# SignalAnalyse.net
KiCad netlist of a schematic drawn in Altium Designer
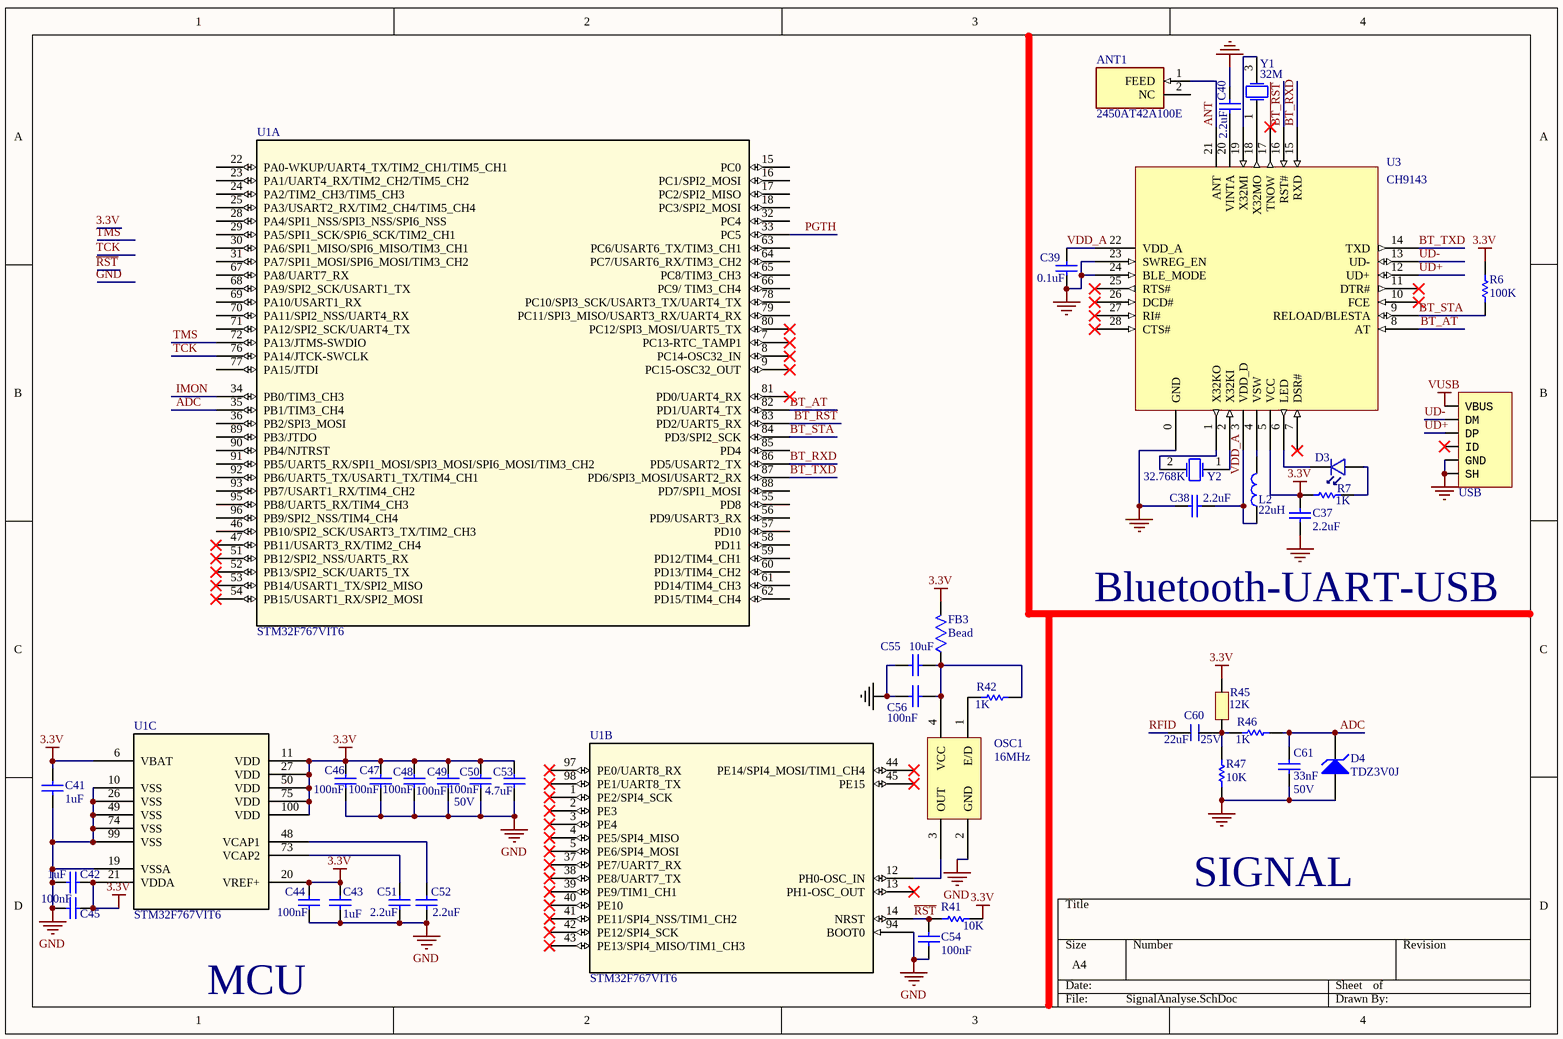
[diagram p0: SignalAnalyse.SchDoc]

(export (version "E")
  (design (tool "Eeschema 10.0.6"))
  (components
    (comp (ref "ANT1")
      (value "2450AT42A100E")
      (footprint "SamacSys:ANTC5020X110N")
      (description "Antenna")
      (fields (field (name "MOUSER PART NUMBER") "609-2450AT42A100E"))
      (libsource (lib "*") (part "2450AT42A100E"))
    )
    (comp (ref "C37")
      (value "2.2uF")
      (footprint "1608[0603]")
      (description "Capacitor (Semiconductor SIM Model)")
      (fields
        (field (name "VOLTAGE") "10V")
        (field (name "Comment") "GRM188R61A226ME15D")
        (field (name "PUBLISHER") "Altium Limited")
      )
      (libsource (lib "Miscellaneous Devices") (part "Cap Semi"))
    )
    (comp (ref "C38")
      (value "2.2uF")
      (footprint "1608[0603]")
      (description "Capacitor (Semiconductor SIM Model)")
      (fields
        (field (name "VOLTAGE") "10V")
        (field (name "Comment") "GRM188R61A226ME15D")
        (field (name "PUBLISHER") "Altium Limited")
      )
      (libsource (lib "Miscellaneous Devices") (part "Cap Semi"))
    )
    (comp (ref "C39")
      (value "0.1uF")
      (footprint "1608[0603]")
      (description "Capacitor (Semiconductor SIM Model)")
      (fields
        (field (name "VOLTAGE") "10V")
        (field (name "Comment") "GRM188R61A226ME15D")
        (field (name "PUBLISHER") "Altium Limited")
      )
      (libsource (lib "Miscellaneous Devices") (part "Cap Semi"))
    )
    (comp (ref "C40")
      (value "2.2uF")
      (footprint "1608[0603]")
      (description "Capacitor (Semiconductor SIM Model)")
      (fields
        (field (name "VOLTAGE") "10V")
        (field (name "Comment") "GRM188R61A226ME15D")
        (field (name "PUBLISHER") "Altium Limited")
      )
      (libsource (lib "Miscellaneous Devices") (part "Cap Semi"))
    )
    (comp (ref "C41")
      (value "1uF")
      (footprint "1608[0603]")
      (description "Capacitor (Semiconductor SIM Model)")
      (fields
        (field (name "VOLTAGE") "50V")
        (field (name "Comment") "GRM188R61A226ME15D")
        (field (name "PUBLISHER") "Altium Limited")
      )
      (libsource (lib "Miscellaneous Devices") (part "Cap Semi"))
    )
    (comp (ref "C42")
      (value "1uF")
      (footprint "1608[0603]")
      (description "Capacitor (Semiconductor SIM Model)")
      (fields
        (field (name "VOLTAGE") "50V")
        (field (name "Comment") "GRM188R61A226ME15D")
        (field (name "PUBLISHER") "Altium Limited")
      )
      (libsource (lib "Miscellaneous Devices") (part "Cap Semi"))
    )
    (comp (ref "C43")
      (value "1uF")
      (footprint "1608[0603]")
      (description "Capacitor (Semiconductor SIM Model)")
      (fields
        (field (name "VOLTAGE") "50V")
        (field (name "Comment") "GRM188R61A226ME15D")
        (field (name "PUBLISHER") "Altium Limited")
      )
      (libsource (lib "Miscellaneous Devices") (part "Cap Semi"))
    )
    (comp (ref "C44")
      (value "100nF")
      (footprint "1608[0603]")
      (description "Capacitor (Semiconductor SIM Model)")
      (fields
        (field (name "VOLTAGE") "50V")
        (field (name "Comment") "GRM188R61A226ME15D")
        (field (name "PUBLISHER") "Altium Limited")
      )
      (libsource (lib "Miscellaneous Devices") (part "Cap Semi"))
    )
    (comp (ref "C45")
      (value "100nF")
      (footprint "1608[0603]")
      (description "Capacitor (Semiconductor SIM Model)")
      (fields
        (field (name "VOLTAGE") "50V")
        (field (name "Comment") "GRM188R61A226ME15D")
        (field (name "PUBLISHER") "Altium Limited")
      )
      (libsource (lib "Miscellaneous Devices") (part "Cap Semi"))
    )
    (comp (ref "C46")
      (value "100nF")
      (footprint "1608[0603]")
      (description "Capacitor (Semiconductor SIM Model)")
      (fields
        (field (name "VOLTAGE") "50V")
        (field (name "Comment") "GRM188R61A226ME15D")
        (field (name "PUBLISHER") "Altium Limited")
      )
      (libsource (lib "Miscellaneous Devices") (part "Cap Semi"))
    )
    (comp (ref "C47")
      (value "100nF")
      (footprint "1608[0603]")
      (description "Capacitor (Semiconductor SIM Model)")
      (fields
        (field (name "VOLTAGE") "50V")
        (field (name "Comment") "GRM188R61A226ME15D")
        (field (name "PUBLISHER") "Altium Limited")
      )
      (libsource (lib "Miscellaneous Devices") (part "Cap Semi"))
    )
    (comp (ref "C48")
      (value "100nF")
      (footprint "1608[0603]")
      (description "Capacitor (Semiconductor SIM Model)")
      (fields
        (field (name "VOLTAGE") "50V")
        (field (name "Comment") "GRM188R61A226ME15D")
        (field (name "PUBLISHER") "Altium Limited")
      )
      (libsource (lib "Miscellaneous Devices") (part "Cap Semi"))
    )
    (comp (ref "C49")
      (value "100nF")
      (footprint "1608[0603]")
      (description "Capacitor (Semiconductor SIM Model)")
      (fields
        (field (name "VOLTAGE") "50V")
        (field (name "Comment") "GRM188R61A226ME15D")
        (field (name "PUBLISHER") "Altium Limited")
      )
      (libsource (lib "Miscellaneous Devices") (part "Cap Semi"))
    )
    (comp (ref "C50")
      (value "100nF")
      (footprint "1608[0603]")
      (description "Capacitor (Semiconductor SIM Model)")
      (fields
        (field (name "VOLTAGE") "50V")
        (field (name "Comment") "GRM188R61A226ME15D")
        (field (name "PUBLISHER") "Altium Limited")
      )
      (libsource (lib "Miscellaneous Devices") (part "Cap Semi"))
    )
    (comp (ref "C51")
      (value "2.2uF")
      (footprint "1608[0603]")
      (description "Capacitor (Semiconductor SIM Model)")
      (fields
        (field (name "VOLTAGE") "16V")
        (field (name "Comment") "GRM188R61A226ME15D")
        (field (name "PUBLISHER") "Altium Limited")
      )
      (libsource (lib "Miscellaneous Devices") (part "Cap Semi"))
    )
    (comp (ref "C52")
      (value "2.2uF")
      (footprint "1608[0603]")
      (description "Capacitor (Semiconductor SIM Model)")
      (fields
        (field (name "VOLTAGE") "16V")
        (field (name "Comment") "GRM188R61A226ME15D")
        (field (name "PUBLISHER") "Altium Limited")
      )
      (libsource (lib "Miscellaneous Devices") (part "Cap Semi"))
    )
    (comp (ref "C53")
      (value "4.7uF")
      (footprint "1608[0603]")
      (description "Capacitor (Semiconductor SIM Model)")
      (fields
        (field (name "VOLTAGE") "10V")
        (field (name "Comment") "GRM188R61A226ME15D")
        (field (name "PUBLISHER") "Altium Limited")
      )
      (libsource (lib "Miscellaneous Devices") (part "Cap Semi"))
    )
    (comp (ref "C54")
      (value "100nF")
      (footprint "1608[0603]")
      (description "Capacitor (Semiconductor SIM Model)")
      (fields
        (field (name "VOLTAGE") "50V")
        (field (name "Comment") "GRM188R61A226ME15D")
        (field (name "PUBLISHER") "Altium Limited")
      )
      (libsource (lib "Miscellaneous Devices") (part "Cap Semi"))
    )
    (comp (ref "C55")
      (value "10uF")
      (footprint "1608[0603]")
      (description "Capacitor (Semiconductor SIM Model)")
      (fields
        (field (name "VOLTAGE") "10V")
        (field (name "PART NUMBER") "GRM188R61E106KA73D")
        (field (name "PUBLISHER") "Altium Limited")
      )
      (libsource (lib "Miscellaneous Devices") (part "Cap Semi"))
    )
    (comp (ref "C56")
      (value "100nF")
      (footprint "1608[0603]")
      (description "Capacitor (Semiconductor SIM Model)")
      (fields
        (field (name "VOLTAGE") "50V")
        (field (name "Comment") "GRM188R61A226ME15D")
        (field (name "PUBLISHER") "Altium Limited")
      )
      (libsource (lib "Miscellaneous Devices") (part "Cap Semi"))
    )
    (comp (ref "C60")
      (value "22uF")
      (footprint "C0805")
      (fields (field (name "VOLTAGE") "25V") (field (name "Comment") "Cap Ceramic"))
      (libsource (lib "Integrated_Library") (part "C-Ceramic"))
    )
    (comp (ref "C61")
      (value "33nF")
      (footprint "1608[0603]")
      (description "Capacitor (Semiconductor SIM Model)")
      (fields
        (field (name "VOLTAGE") "50V")
        (field (name "Comment") "Cap Semi")
        (field (name "PUBLISHER") "Altium Limited")
      )
      (libsource (lib "Miscellaneous Devices") (part "Cap Semi"))
    )
    (comp (ref "D3")
      (value "LED-Green")
      (footprint "D0805")
      (libsource (lib "Integrated_Library") (part "LED"))
    )
    (comp (ref "D4")
      (value "TDZ3V0J")
      (footprint "SOD-323")
      (description "Zener Diode 3V")
      (fields (field (name "PUBLISHER") "Altium Limited"))
      (libsource (lib "Miscellaneous Devices") (part "D Zener"))
    )
    (comp (ref "FB3")
      (value "Bead")
      (footprint "SamacSys:BEADC2012X110N")
      (description "Wurth Ferrite Bead")
      (fields (field (name "MANUFACTURER_PART_NUMBER") "782853200"))
      (libsource (lib "SamacSys") (part "782853200"))
    )
    (comp (ref "L2")
      (value "22uH")
      (footprint "L0805")
      (fields (field (name "PART NUMBER") "MGFL2012F220") (field (name "MANUFACTURER") "microgate"))
      (libsource (lib "Integrated_Library") (part "FB"))
    )
    (comp (ref "OSC1")
      (value "16MHz")
      (footprint "OSC_3.2X2.5")
      (description "OSC with disable function")
      (libsource (lib "Integrated_Library") (part "OSC2"))
    )
    (comp (ref "R6")
      (value "100K")
      (footprint "J1-0603")
      (description "Resistor")
      (fields
        (field (name "PART NUMBER") "RC0603FR-07100KL")
        (field (name "MANUFACTURER") "YAGEO")
        (field (name "PUBLISHER") "Altium Limited")
      )
      (libsource (lib "Miscellaneous Devices") (part "Res1"))
    )
    (comp (ref "R7")
      (value "1K")
      (footprint "J1-0603")
      (description "Resistor")
      (fields
        (field (name "PART NUMBER") "RC0603FR-071KL")
        (field (name "MANUFACTURER") "YAGEO")
        (field (name "PUBLISHER") "Altium Limited")
      )
      (libsource (lib "Miscellaneous Devices") (part "Res1"))
    )
    (comp (ref "R41")
      (value "10K")
      (footprint "J1-0603")
      (description "Resistor")
      (fields
        (field (name "PART NUMBER") "RC0603FR-0710KL")
        (field (name "MANUFACTURER") "YAGEO")
        (field (name "PUBLISHER") "Altium Limited")
      )
      (libsource (lib "Miscellaneous Devices") (part "Res1"))
    )
    (comp (ref "R42")
      (value "1K")
      (footprint "J1-0603")
      (description "Resistor")
      (fields
        (field (name "PART NUMBER") "RC0603FR-071KL")
        (field (name "MANUFACTURER") "YAGEO")
        (field (name "PUBLISHER") "Altium Limited")
      )
      (libsource (lib "Miscellaneous Devices") (part "Res1"))
    )
    (comp (ref "R45")
      (value "12K")
      (footprint "R0805")
      (fields
        (field (name "PART NUMBER") "RC0805FR-0712KL")
        (field (name "MANUFACTURER") "YAGEO")
        (field (name "Comment") "R")
      )
      (libsource (lib "Integrated_Library") (part "Res SMT"))
    )
    (comp (ref "R46")
      (value "1K")
      (footprint "J1-0603")
      (description "Resistor")
      (fields
        (field (name "PART NUMBER") "RC0603FR-071KL")
        (field (name "MANUFACTURER") "YAGEO")
        (field (name "PUBLISHER") "Altium Limited")
      )
      (libsource (lib "Miscellaneous Devices") (part "Res1"))
    )
    (comp (ref "R47")
      (value "10K")
      (footprint "J1-0603")
      (description "Resistor")
      (fields
        (field (name "PART NUMBER") "RC0603FR-0710KL")
        (field (name "MANUFACTURER") "YAGEO")
        (field (name "PUBLISHER") "Altium Limited")
      )
      (libsource (lib "Miscellaneous Devices") (part "Res1"))
    )
    (comp (ref "U1")
      (value "STM32F767VIT6")
      (footprint "STM32F767VIT6")
      (description "Imported")
      (fields
        (field (name "MANUFACTURER_PART_NUMBER") "stm32f76xvxt")
        (field (name "COPYRIGHT") "Copyright (C) 2016 Accelerated Designs. All rights reserved")
      )
      (libsource (lib "Integrated_Library") (part "STM32F76XVXT"))
    )
    (comp (ref "U3")
      (value "CH9143")
      (footprint "QFN28_4X4")
      (description "Bluetooth-LowEnergy & UART & USB Mutual Transport")
      (libsource (lib "CHXXX") (part "CH9143"))
    )
    (comp (ref "USB")
      (value "MicroUSB")
      (footprint "PCB_USB:USB_Micro-AB")
      (description "USB")
      (libsource (lib "SCH_USB") (part "USB_Micro"))
    )
    (comp (ref "Y1")
      (value "32M")
      (footprint "SamacSys:SMD2016-4N")
      (description "Quartz Crystal Oscillator")
      (fields (field (name "MANUFACTURER_PART_NUMBER") "X201632MMB4SI"))
      (libsource (lib "SamacSys") (part "X201632MMB4SI"))
    )
    (comp (ref "Y2")
      (value "32.768K")
      (footprint "SamacSys:Q13FC1350000400")
      (description "Crystal Oscillator")
      (fields (field (name "MANUFACTURER_PART_NUMBER") "Q13FC1350000400"))
      (libsource (lib "SamacSys") (part "Q13FC1350000400"))
    )
  )
  (nets
    (net (code "1") (name "/ADC") (class "Default")
      (node (ref "C61") (pin "2") (pinfunction "2_2") (pintype "passive"))
      (node (ref "D4") (pin "2") (pinfunction "K_2") (pintype "passive"))
      (node (ref "R46") (pin "2") (pinfunction "2_2") (pintype "passive"))
      (node (ref "U1") (pin "35") (pinfunction "PB1/TIM3_CH4_35") (pintype "bidirectional"))
    )
    (net (code "2") (name "/ANT") (class "Default")
      (node (ref "ANT1") (pin "1") (pinfunction "FEED_1") (pintype "input"))
      (node (ref "U3") (pin "21") (pinfunction "ANT_21") (pintype "passive"))
    )
    (net (code "3") (name "/BT_AT") (class "Default")
      (node (ref "U1") (pin "82") (pinfunction "PD1/UART4_TX_82") (pintype "bidirectional"))
      (node (ref "U3") (pin "8") (pinfunction "AT_8") (pintype "input"))
    )
    (net (code "4") (name "/BT_RXD") (class "Default")
      (node (ref "U1") (pin "86") (pinfunction "PD5/USART2_TX_86") (pintype "bidirectional"))
      (node (ref "U3") (pin "15") (pinfunction "RXD_15") (pintype "input"))
    )
    (net (code "5") (name "/BT_STA") (class "Default")
      (node (ref "R6") (pin "2") (pinfunction "2_2") (pintype "passive"))
      (node (ref "U1") (pin "84") (pinfunction "PD3/SPI2_SCK_84") (pintype "bidirectional"))
      (node (ref "U3") (pin "9") (pinfunction "RELOAD/BLESTA_9") (pintype "bidirectional"))
    )
    (net (code "6") (name "/BT_TXD") (class "Default")
      (node (ref "U1") (pin "87") (pinfunction "PD6/SPI3_MOSI/USART2_RX_87") (pintype "bidirectional"))
      (node (ref "U3") (pin "14") (pinfunction "TXD_14") (pintype "output"))
    )
    (net (code "7") (name "/IMON") (class "Default")
      (node (ref "U1") (pin "34") (pinfunction "PB0/TIM3_CH3_34") (pintype "bidirectional"))
    )
    (net (code "8") (name "/PGTH") (class "Default")
      (node (ref "U1") (pin "33") (pinfunction "PC5_33") (pintype "bidirectional"))
    )
    (net (code "9") (name "/RFID") (class "Default")
      (node (ref "C60") (pin "1") (pinfunction "1_1") (pintype "passive"))
    )
    (net (code "10") (name "/TCK") (class "Default")
      (node (ref "U1") (pin "76") (pinfunction "PA14/JTCK-SWCLK_76") (pintype "bidirectional"))
    )
    (net (code "11") (name "/TMS") (class "Default")
      (node (ref "U1") (pin "72") (pinfunction "PA13/JTMS-SWDIO_72") (pintype "bidirectional"))
    )
    (net (code "12") (name "/UD+") (class "Default")
      (node (ref "U3") (pin "12") (pinfunction "UD+_12") (pintype "bidirectional"))
      (node (ref "USB") (pin "3") (pinfunction "DP_3") (pintype "passive"))
    )
    (net (code "13") (name "/UD-") (class "Default")
      (node (ref "U3") (pin "13") (pinfunction "UD-_13") (pintype "bidirectional"))
      (node (ref "USB") (pin "2") (pinfunction "DM_2") (pintype "passive"))
    )
    (net (code "14") (name "/VDD_A") (class "Default")
      (node (ref "C38") (pin "2") (pinfunction "2_2") (pintype "passive"))
      (node (ref "C39") (pin "1") (pinfunction "1_1") (pintype "passive"))
      (node (ref "L2") (pin "1") (pinfunction "1_1") (pintype "passive"))
      (node (ref "U3") (pin "22") (pinfunction "VDD_A_22") (pintype "power_in"))
      (node (ref "U3") (pin "3") (pinfunction "VDD_D_3") (pintype "power_in"))
    )
    (net (code "15") (name "/~{BT_RST}") (class "Default")
      (node (ref "U1") (pin "83") (pinfunction "PD2/UART5_RX_83") (pintype "bidirectional"))
      (node (ref "U3") (pin "16") (pinfunction "RST#_16") (pintype "input"))
    )
    (net (code "16") (name "/~{RST}") (class "Default")
      (node (ref "C54") (pin "1") (pinfunction "1_1") (pintype "passive"))
      (node (ref "R41") (pin "1") (pinfunction "1_1") (pintype "passive"))
      (node (ref "U1") (pin "14") (pinfunction "NRST_14") (pintype "bidirectional"))
    )
    (net (code "17") (name "3.3V") (class "Default")
      (node (ref "C37") (pin "2") (pinfunction "2_2") (pintype "passive"))
      (node (ref "C41") (pin "1") (pinfunction "1_1") (pintype "passive"))
      (node (ref "C42") (pin "1") (pinfunction "1_1") (pintype "passive"))
      (node (ref "C43") (pin "2") (pinfunction "2_2") (pintype "passive"))
      (node (ref "C44") (pin "2") (pinfunction "2_2") (pintype "passive"))
      (node (ref "C45") (pin "1") (pinfunction "1_1") (pintype "passive"))
      (node (ref "C46") (pin "2") (pinfunction "2_2") (pintype "passive"))
      (node (ref "C47") (pin "2") (pinfunction "2_2") (pintype "passive"))
      (node (ref "C48") (pin "2") (pinfunction "2_2") (pintype "passive"))
      (node (ref "C49") (pin "2") (pinfunction "2_2") (pintype "passive"))
      (node (ref "C50") (pin "2") (pinfunction "2_2") (pintype "passive"))
      (node (ref "C53") (pin "2") (pinfunction "2_2") (pintype "passive"))
      (node (ref "FB3") (pin "2") (pinfunction "2_2") (pintype "passive"))
      (node (ref "R41") (pin "2") (pinfunction "2_2") (pintype "passive"))
      (node (ref "R45") (pin "2") (pinfunction "2_2") (pintype "passive"))
      (node (ref "R6") (pin "1") (pinfunction "1_1") (pintype "passive"))
      (node (ref "R7") (pin "1") (pinfunction "1_1") (pintype "passive"))
      (node (ref "U1") (pin "100") (pinfunction "VDD_100") (pintype "power_in"))
      (node (ref "U1") (pin "11") (pinfunction "VDD_11") (pintype "power_in"))
      (node (ref "U1") (pin "20") (pinfunction "VREF+_20") (pintype "power_in"))
      (node (ref "U1") (pin "21") (pinfunction "VDDA_21") (pintype "power_in"))
      (node (ref "U1") (pin "27") (pinfunction "VDD_27") (pintype "power_in"))
      (node (ref "U1") (pin "50") (pinfunction "VDD_50") (pintype "power_in"))
      (node (ref "U1") (pin "6") (pinfunction "VBAT_6") (pintype "power_in"))
      (node (ref "U1") (pin "75") (pinfunction "VDD_75") (pintype "power_in"))
      (node (ref "U3") (pin "5") (pinfunction "VCC_5") (pintype "power_in"))
    )
    (net (code "18") (name "GND") (class "Default")
      (node (ref "C37") (pin "1") (pinfunction "1_1") (pintype "passive"))
      (node (ref "C38") (pin "1") (pinfunction "1_1") (pintype "passive"))
      (node (ref "C39") (pin "2") (pinfunction "2_2") (pintype "passive"))
      (node (ref "C40") (pin "1") (pinfunction "1_1") (pintype "passive"))
      (node (ref "C41") (pin "2") (pinfunction "2_2") (pintype "passive"))
      (node (ref "C42") (pin "2") (pinfunction "2_2") (pintype "passive"))
      (node (ref "C43") (pin "1") (pinfunction "1_1") (pintype "passive"))
      (node (ref "C44") (pin "1") (pinfunction "1_1") (pintype "passive"))
      (node (ref "C45") (pin "2") (pinfunction "2_2") (pintype "passive"))
      (node (ref "C46") (pin "1") (pinfunction "1_1") (pintype "passive"))
      (node (ref "C47") (pin "1") (pinfunction "1_1") (pintype "passive"))
      (node (ref "C48") (pin "1") (pinfunction "1_1") (pintype "passive"))
      (node (ref "C49") (pin "1") (pinfunction "1_1") (pintype "passive"))
      (node (ref "C50") (pin "1") (pinfunction "1_1") (pintype "passive"))
      (node (ref "C51") (pin "1") (pinfunction "1_1") (pintype "passive"))
      (node (ref "C52") (pin "1") (pinfunction "1_1") (pintype "passive"))
      (node (ref "C53") (pin "1") (pinfunction "1_1") (pintype "passive"))
      (node (ref "C54") (pin "2") (pinfunction "2_2") (pintype "passive"))
      (node (ref "C55") (pin "2") (pinfunction "2_2") (pintype "passive"))
      (node (ref "C56") (pin "2") (pinfunction "2_2") (pintype "passive"))
      (node (ref "C61") (pin "1") (pinfunction "1_1") (pintype "passive"))
      (node (ref "D4") (pin "1") (pinfunction "A_1") (pintype "passive"))
      (node (ref "OSC1") (pin "2") (pinfunction "GND_2") (pintype "passive"))
      (node (ref "R47") (pin "2") (pinfunction "2_2") (pintype "passive"))
      (node (ref "U1") (pin "10") (pinfunction "VSS_10") (pintype "power_in"))
      (node (ref "U1") (pin "19") (pinfunction "VSSA_19") (pintype "power_in"))
      (node (ref "U1") (pin "26") (pinfunction "VSS_26") (pintype "power_in"))
      (node (ref "U1") (pin "49") (pinfunction "VSS_49") (pintype "power_in"))
      (node (ref "U1") (pin "74") (pinfunction "VSS_74") (pintype "power_in"))
      (node (ref "U1") (pin "94") (pinfunction "BOOT0_94") (pintype "input"))
      (node (ref "U1") (pin "99") (pinfunction "VSS_99") (pintype "power_in"))
      (node (ref "U3") (pin "0") (pinfunction "GND_0") (pintype "power_in"))
      (node (ref "U3") (pin "23") (pinfunction "SWREG_EN_23") (pintype "input"))
      (node (ref "U3") (pin "24") (pinfunction "BLE_MODE_24") (pintype "input"))
      (node (ref "USB") (pin "0") (pinfunction "SH_0") (pintype "passive"))
      (node (ref "USB") (pin "5") (pinfunction "GND_5") (pintype "passive"))
    )
    (net (code "19") (name "Net-(C60-Pad2)") (class "Default")
      (node (ref "C60") (pin "2") (pinfunction "2_2") (pintype "passive"))
      (node (ref "R45") (pin "1") (pinfunction "1_1") (pintype "passive"))
      (node (ref "R46") (pin "1") (pinfunction "1_1") (pintype "passive"))
      (node (ref "R47") (pin "1") (pinfunction "1_1") (pintype "passive"))
    )
    (net (code "20") (name "Net-(D3-Pad1)") (class "Default")
      (node (ref "D3") (pin "1") (pinfunction "1_1") (pintype "passive"))
      (node (ref "R7") (pin "2") (pinfunction "2_2") (pintype "passive"))
    )
    (net (code "21") (name "Net-(OSC1-E{slash}D)") (class "Default")
      (node (ref "OSC1") (pin "1") (pinfunction "E/D_1") (pintype "passive"))
      (node (ref "R42") (pin "1") (pinfunction "1_1") (pintype "passive"))
    )
    (net (code "22") (name "Net-(OSC1-OUT)") (class "Default")
      (node (ref "OSC1") (pin "3") (pinfunction "OUT_3") (pintype "passive"))
      (node (ref "U1") (pin "12") (pinfunction "PH0-OSC_IN_12") (pintype "bidirectional"))
    )
    (net (code "23") (name "Net-(OSC1-VCC)") (class "Default")
      (node (ref "C55") (pin "1") (pinfunction "1_1") (pintype "passive"))
      (node (ref "C56") (pin "1") (pinfunction "1_1") (pintype "passive"))
      (node (ref "FB3") (pin "1") (pinfunction "1_1") (pintype "passive"))
      (node (ref "OSC1") (pin "4") (pinfunction "VCC_4") (pintype "passive"))
      (node (ref "R42") (pin "2") (pinfunction "2_2") (pintype "passive"))
    )
    (net (code "24") (name "Net-(U1C-VCAP1)") (class "Default")
      (node (ref "C52") (pin "2") (pinfunction "2_2") (pintype "passive"))
      (node (ref "U1") (pin "48") (pinfunction "VCAP1_48") (pintype "power_in"))
    )
    (net (code "25") (name "Net-(U1C-VCAP2)") (class "Default")
      (node (ref "C51") (pin "2") (pinfunction "2_2") (pintype "passive"))
      (node (ref "U1") (pin "73") (pinfunction "VCAP2_73") (pintype "power_in"))
    )
    (net (code "26") (name "Net-(U3-LED)") (class "Default")
      (node (ref "D3") (pin "2") (pinfunction "2_2") (pintype "passive"))
      (node (ref "U3") (pin "6") (pinfunction "LED_6") (pintype "output"))
    )
    (net (code "27") (name "Net-(U3-VINTA)") (class "Default")
      (node (ref "C40") (pin "2") (pinfunction "2_2") (pintype "passive"))
      (node (ref "U3") (pin "20") (pinfunction "VINTA_20") (pintype "power_in"))
    )
    (net (code "28") (name "Net-(U3-VSW)") (class "Default")
      (node (ref "L2") (pin "2") (pinfunction "2_2") (pintype "passive"))
      (node (ref "U3") (pin "4") (pinfunction "VSW_4") (pintype "power_in"))
    )
    (net (code "29") (name "Net-(U3-X32KI)") (class "Default")
      (node (ref "U3") (pin "2") (pinfunction "X32KI_2") (pintype "input"))
      (node (ref "Y2") (pin "1") (pinfunction "CRYSTAL_1_1") (pintype "passive"))
    )
    (net (code "30") (name "Net-(U3-X32KO)") (class "Default")
      (node (ref "U3") (pin "1") (pinfunction "X32KO_1") (pintype "output"))
      (node (ref "Y2") (pin "2") (pinfunction "CRYSTAL_2_2") (pintype "passive"))
    )
    (net (code "31") (name "Net-(U3-X32MI)") (class "Default")
      (node (ref "U3") (pin "19") (pinfunction "X32MI_19") (pintype "input"))
      (node (ref "Y1") (pin "3") (pinfunction "OSC2_3") (pintype "passive"))
    )
    (net (code "32") (name "Net-(U3-X32MO)") (class "Default")
      (node (ref "U3") (pin "18") (pinfunction "X32MO_18") (pintype "output"))
      (node (ref "Y1") (pin "1") (pinfunction "OSC1_1") (pintype "passive"))
    )
    (net (code "33") (name "VUSB") (class "Default")
      (node (ref "USB") (pin "1") (pinfunction "VBUS_1") (pintype "passive"))
    )
    (net (code "34") (name "unconnected-(ANT1-NC-Pad2)") (class "Default")
      (node (ref "ANT1") (pin "2") (pinfunction "NC_2") (pintype "passive"))
    )
    (net (code "35") (name "unconnected-(U1A-PA0-WKUP{slash}UART4_TX{slash}TIM2_CH1{slash}TIM5_CH1-Pad22)") (class "Default")
      (node (ref "U1") (pin "22") (pinfunction "PA0-WKUP/UART4_TX/TIM2_CH1/TIM5_CH1_22") (pintype "bidirectional"))
    )
    (net (code "36") (name "unconnected-(U1A-PA1{slash}UART4_RX{slash}TIM2_CH2{slash}TIM5_CH2-Pad23)") (class "Default")
      (node (ref "U1") (pin "23") (pinfunction "PA1/UART4_RX/TIM2_CH2/TIM5_CH2_23") (pintype "bidirectional"))
    )
    (net (code "37") (name "unconnected-(U1A-PA2{slash}TIM2_CH3{slash}TIM5_CH3-Pad24)") (class "Default")
      (node (ref "U1") (pin "24") (pinfunction "PA2/TIM2_CH3/TIM5_CH3_24") (pintype "bidirectional"))
    )
    (net (code "38") (name "unconnected-(U1A-PA3{slash}USART2_RX{slash}TIM2_CH4{slash}TIM5_CH4-Pad25)") (class "Default")
      (node (ref "U1") (pin "25") (pinfunction "PA3/USART2_RX/TIM2_CH4/TIM5_CH4_25") (pintype "bidirectional"))
    )
    (net (code "39") (name "unconnected-(U1A-PA4{slash}SPI1_NSS{slash}SPI3_NSS{slash}SPI6_NSS-Pad28)") (class "Default")
      (node (ref "U1") (pin "28") (pinfunction "PA4/SPI1_NSS/SPI3_NSS/SPI6_NSS_28") (pintype "bidirectional"))
    )
    (net (code "40") (name "unconnected-(U1A-PA5{slash}SPI1_SCK{slash}SPI6_SCK{slash}TIM2_CH1-Pad29)") (class "Default")
      (node (ref "U1") (pin "29") (pinfunction "PA5/SPI1_SCK/SPI6_SCK/TIM2_CH1_29") (pintype "bidirectional"))
    )
    (net (code "41") (name "unconnected-(U1A-PA6{slash}SPI1_MISO{slash}SPI6_MISO{slash}TIM3_CH1-Pad30)") (class "Default")
      (node (ref "U1") (pin "30") (pinfunction "PA6/SPI1_MISO/SPI6_MISO/TIM3_CH1_30") (pintype "bidirectional"))
    )
    (net (code "42") (name "unconnected-(U1A-PA7{slash}SPI1_MOSI{slash}SPI6_MOSI{slash}TIM3_CH2-Pad31)") (class "Default")
      (node (ref "U1") (pin "31") (pinfunction "PA7/SPI1_MOSI/SPI6_MOSI/TIM3_CH2_31") (pintype "bidirectional"))
    )
    (net (code "43") (name "unconnected-(U1A-PA8{slash}UART7_RX-Pad67)") (class "Default")
      (node (ref "U1") (pin "67") (pinfunction "PA8/UART7_RX_67") (pintype "bidirectional"))
    )
    (net (code "44") (name "unconnected-(U1A-PA9{slash}SPI2_SCK{slash}USART1_TX-Pad68)") (class "Default")
      (node (ref "U1") (pin "68") (pinfunction "PA9/SPI2_SCK/USART1_TX_68") (pintype "bidirectional"))
    )
    (net (code "45") (name "unconnected-(U1A-PA10{slash}USART1_RX-Pad69)") (class "Default")
      (node (ref "U1") (pin "69") (pinfunction "PA10/USART1_RX_69") (pintype "bidirectional"))
    )
    (net (code "46") (name "unconnected-(U1A-PA11{slash}SPI2_NSS{slash}UART4_RX-Pad70)") (class "Default")
      (node (ref "U1") (pin "70") (pinfunction "PA11/SPI2_NSS/UART4_RX_70") (pintype "bidirectional"))
    )
    (net (code "47") (name "unconnected-(U1A-PA12{slash}SPI2_SCK{slash}UART4_TX-Pad71)") (class "Default")
      (node (ref "U1") (pin "71") (pinfunction "PA12/SPI2_SCK/UART4_TX_71") (pintype "bidirectional"))
    )
    (net (code "48") (name "unconnected-(U1A-PA15{slash}JTDI-Pad77)") (class "Default")
      (node (ref "U1") (pin "77") (pinfunction "PA15/JTDI_77") (pintype "bidirectional"))
    )
    (net (code "49") (name "unconnected-(U1A-PB2{slash}SPI3_MOSI-Pad36)") (class "Default")
      (node (ref "U1") (pin "36") (pinfunction "PB2/SPI3_MOSI_36") (pintype "bidirectional"))
    )
    (net (code "50") (name "unconnected-(U1A-PB3{slash}JTDO-Pad89)") (class "Default")
      (node (ref "U1") (pin "89") (pinfunction "PB3/JTDO_89") (pintype "bidirectional"))
    )
    (net (code "51") (name "unconnected-(U1A-PB4{slash}NJTRST-Pad90)") (class "Default")
      (node (ref "U1") (pin "90") (pinfunction "PB4/NJTRST_90") (pintype "bidirectional"))
    )
    (net (code "52") (name "unconnected-(U1A-PB5{slash}UART5_RX{slash}SPI1_MOSI{slash}SPI3_MOSI{slash}SPI6_MOSI{slash}TIM3_CH2-Pad91)") (class "Default")
      (node (ref "U1") (pin "91") (pinfunction "PB5/UART5_RX/SPI1_MOSI/SPI3_MOSI/SPI6_MOSI/TIM3_CH2_91") (pintype "bidirectional"))
    )
    (net (code "53") (name "unconnected-(U1A-PB6{slash}UART5_TX{slash}USART1_TX{slash}TIM4_CH1-Pad92)") (class "Default")
      (node (ref "U1") (pin "92") (pinfunction "PB6/UART5_TX/USART1_TX/TIM4_CH1_92") (pintype "bidirectional"))
    )
    (net (code "54") (name "unconnected-(U1A-PB7{slash}USART1_RX{slash}TIM4_CH2-Pad93)") (class "Default")
      (node (ref "U1") (pin "93") (pinfunction "PB7/USART1_RX/TIM4_CH2_93") (pintype "bidirectional"))
    )
    (net (code "55") (name "unconnected-(U1A-PB8{slash}UART5_RX{slash}TIM4_CH3-Pad95)") (class "Default")
      (node (ref "U1") (pin "95") (pinfunction "PB8/UART5_RX/TIM4_CH3_95") (pintype "bidirectional"))
    )
    (net (code "56") (name "unconnected-(U1A-PB9{slash}SPI2_NSS{slash}TIM4_CH4-Pad96)") (class "Default")
      (node (ref "U1") (pin "96") (pinfunction "PB9/SPI2_NSS/TIM4_CH4_96") (pintype "bidirectional"))
    )
    (net (code "57") (name "unconnected-(U1A-PB10{slash}SPI2_SCK{slash}USART3_TX{slash}TIM2_CH3-Pad46)") (class "Default")
      (node (ref "U1") (pin "46") (pinfunction "PB10/SPI2_SCK/USART3_TX/TIM2_CH3_46") (pintype "bidirectional"))
    )
    (net (code "58") (name "unconnected-(U1A-PB11{slash}USART3_RX{slash}TIM2_CH4-Pad47)") (class "Default")
      (node (ref "U1") (pin "47") (pinfunction "PB11/USART3_RX/TIM2_CH4_47") (pintype "bidirectional+no_connect"))
    )
    (net (code "59") (name "unconnected-(U1A-PB12{slash}SPI2_NSS{slash}UART5_RX-Pad51)") (class "Default")
      (node (ref "U1") (pin "51") (pinfunction "PB12/SPI2_NSS/UART5_RX_51") (pintype "bidirectional+no_connect"))
    )
    (net (code "60") (name "unconnected-(U1A-PB13{slash}SPI2_SCK{slash}UART5_TX-Pad52)") (class "Default")
      (node (ref "U1") (pin "52") (pinfunction "PB13/SPI2_SCK/UART5_TX_52") (pintype "bidirectional+no_connect"))
    )
    (net (code "61") (name "unconnected-(U1A-PB14{slash}USART1_TX{slash}SPI2_MISO-Pad53)") (class "Default")
      (node (ref "U1") (pin "53") (pinfunction "PB14/USART1_TX/SPI2_MISO_53") (pintype "bidirectional+no_connect"))
    )
    (net (code "62") (name "unconnected-(U1A-PB15{slash}USART1_RX{slash}SPI2_MOSI-Pad54)") (class "Default")
      (node (ref "U1") (pin "54") (pinfunction "PB15/USART1_RX/SPI2_MOSI_54") (pintype "bidirectional+no_connect"))
    )
    (net (code "63") (name "unconnected-(U1A-PC0-Pad15)") (class "Default")
      (node (ref "U1") (pin "15") (pinfunction "PC0_15") (pintype "bidirectional"))
    )
    (net (code "64") (name "unconnected-(U1A-PC1{slash}SPI2_MOSI-Pad16)") (class "Default")
      (node (ref "U1") (pin "16") (pinfunction "PC1/SPI2_MOSI_16") (pintype "bidirectional"))
    )
    (net (code "65") (name "unconnected-(U1A-PC2{slash}SPI2_MISO-Pad17)") (class "Default")
      (node (ref "U1") (pin "17") (pinfunction "PC2/SPI2_MISO_17") (pintype "bidirectional"))
    )
    (net (code "66") (name "unconnected-(U1A-PC3{slash}SPI2_MOSI-Pad18)") (class "Default")
      (node (ref "U1") (pin "18") (pinfunction "PC3/SPI2_MOSI_18") (pintype "bidirectional"))
    )
    (net (code "67") (name "unconnected-(U1A-PC4-Pad32)") (class "Default")
      (node (ref "U1") (pin "32") (pinfunction "PC4_32") (pintype "bidirectional"))
    )
    (net (code "68") (name "unconnected-(U1A-PC6{slash}USART6_TX{slash}TIM3_CH1-Pad63)") (class "Default")
      (node (ref "U1") (pin "63") (pinfunction "PC6/USART6_TX/TIM3_CH1_63") (pintype "bidirectional"))
    )
    (net (code "69") (name "unconnected-(U1A-PC7{slash}USART6_RX{slash}TIM3_CH2-Pad64)") (class "Default")
      (node (ref "U1") (pin "64") (pinfunction "PC7/USART6_RX/TIM3_CH2_64") (pintype "bidirectional"))
    )
    (net (code "70") (name "unconnected-(U1A-PC8{slash}TIM3_CH3-Pad65)") (class "Default")
      (node (ref "U1") (pin "65") (pinfunction "PC8/TIM3_CH3_65") (pintype "bidirectional"))
    )
    (net (code "71") (name "unconnected-(U1A-PC9{slash}_TIM3_CH4-Pad66)") (class "Default")
      (node (ref "U1") (pin "66") (pinfunction "PC9/_TIM3_CH4_66") (pintype "bidirectional"))
    )
    (net (code "72") (name "unconnected-(U1A-PC10{slash}SPI3_SCK{slash}USART3_TX{slash}UART4_TX-Pad78)") (class "Default")
      (node (ref "U1") (pin "78") (pinfunction "PC10/SPI3_SCK/USART3_TX/UART4_TX_78") (pintype "bidirectional"))
    )
    (net (code "73") (name "unconnected-(U1A-PC11{slash}SPI3_MISO{slash}USART3_RX{slash}UART4_RX-Pad79)") (class "Default")
      (node (ref "U1") (pin "79") (pinfunction "PC11/SPI3_MISO/USART3_RX/UART4_RX_79") (pintype "bidirectional"))
    )
    (net (code "74") (name "unconnected-(U1A-PC12{slash}SPI3_MOSI{slash}UART5_TX-Pad80)") (class "Default")
      (node (ref "U1") (pin "80") (pinfunction "PC12/SPI3_MOSI/UART5_TX_80") (pintype "bidirectional+no_connect"))
    )
    (net (code "75") (name "unconnected-(U1A-PC13-RTC_TAMP1-Pad7)") (class "Default")
      (node (ref "U1") (pin "7") (pinfunction "PC13-RTC_TAMP1_7") (pintype "bidirectional+no_connect"))
    )
    (net (code "76") (name "unconnected-(U1A-PC14-OSC32_IN-Pad8)") (class "Default")
      (node (ref "U1") (pin "8") (pinfunction "PC14-OSC32_IN_8") (pintype "bidirectional+no_connect"))
    )
    (net (code "77") (name "unconnected-(U1A-PC15-OSC32_OUT-Pad9)") (class "Default")
      (node (ref "U1") (pin "9") (pinfunction "PC15-OSC32_OUT_9") (pintype "bidirectional+no_connect"))
    )
    (net (code "78") (name "unconnected-(U1A-PD0{slash}UART4_RX-Pad81)") (class "Default")
      (node (ref "U1") (pin "81") (pinfunction "PD0/UART4_RX_81") (pintype "bidirectional+no_connect"))
    )
    (net (code "79") (name "unconnected-(U1A-PD4-Pad85)") (class "Default")
      (node (ref "U1") (pin "85") (pinfunction "PD4_85") (pintype "bidirectional"))
    )
    (net (code "80") (name "unconnected-(U1A-PD7{slash}SPI1_MOSI-Pad88)") (class "Default")
      (node (ref "U1") (pin "88") (pinfunction "PD7/SPI1_MOSI_88") (pintype "bidirectional"))
    )
    (net (code "81") (name "unconnected-(U1A-PD8-Pad55)") (class "Default")
      (node (ref "U1") (pin "55") (pinfunction "PD8_55") (pintype "bidirectional"))
    )
    (net (code "82") (name "unconnected-(U1A-PD9{slash}USART3_RX-Pad56)") (class "Default")
      (node (ref "U1") (pin "56") (pinfunction "PD9/USART3_RX_56") (pintype "bidirectional"))
    )
    (net (code "83") (name "unconnected-(U1A-PD10-Pad57)") (class "Default")
      (node (ref "U1") (pin "57") (pinfunction "PD10_57") (pintype "bidirectional"))
    )
    (net (code "84") (name "unconnected-(U1A-PD11-Pad58)") (class "Default")
      (node (ref "U1") (pin "58") (pinfunction "PD11_58") (pintype "bidirectional"))
    )
    (net (code "85") (name "unconnected-(U1A-PD12{slash}TIM4_CH1-Pad59)") (class "Default")
      (node (ref "U1") (pin "59") (pinfunction "PD12/TIM4_CH1_59") (pintype "bidirectional"))
    )
    (net (code "86") (name "unconnected-(U1A-PD13{slash}TIM4_CH2-Pad60)") (class "Default")
      (node (ref "U1") (pin "60") (pinfunction "PD13/TIM4_CH2_60") (pintype "bidirectional"))
    )
    (net (code "87") (name "unconnected-(U1A-PD14{slash}TIM4_CH3-Pad61)") (class "Default")
      (node (ref "U1") (pin "61") (pinfunction "PD14/TIM4_CH3_61") (pintype "bidirectional"))
    )
    (net (code "88") (name "unconnected-(U1A-PD15{slash}TIM4_CH4-Pad62)") (class "Default")
      (node (ref "U1") (pin "62") (pinfunction "PD15/TIM4_CH4_62") (pintype "bidirectional"))
    )
    (net (code "89") (name "unconnected-(U1B-PE0{slash}UART8_RX-Pad97)") (class "Default")
      (node (ref "U1") (pin "97") (pinfunction "PE0/UART8_RX_97") (pintype "bidirectional+no_connect"))
    )
    (net (code "90") (name "unconnected-(U1B-PE1{slash}UART8_TX-Pad98)") (class "Default")
      (node (ref "U1") (pin "98") (pinfunction "PE1/UART8_TX_98") (pintype "bidirectional+no_connect"))
    )
    (net (code "91") (name "unconnected-(U1B-PE2{slash}SPI4_SCK-Pad1)") (class "Default")
      (node (ref "U1") (pin "1") (pinfunction "PE2/SPI4_SCK_1") (pintype "bidirectional+no_connect"))
    )
    (net (code "92") (name "unconnected-(U1B-PE3-Pad2)") (class "Default")
      (node (ref "U1") (pin "2") (pinfunction "PE3_2") (pintype "bidirectional+no_connect"))
    )
    (net (code "93") (name "unconnected-(U1B-PE4-Pad3)") (class "Default")
      (node (ref "U1") (pin "3") (pinfunction "PE4_3") (pintype "bidirectional+no_connect"))
    )
    (net (code "94") (name "unconnected-(U1B-PE5{slash}SPI4_MISO-Pad4)") (class "Default")
      (node (ref "U1") (pin "4") (pinfunction "PE5/SPI4_MISO_4") (pintype "bidirectional+no_connect"))
    )
    (net (code "95") (name "unconnected-(U1B-PE6{slash}SPI4_MOSI-Pad5)") (class "Default")
      (node (ref "U1") (pin "5") (pinfunction "PE6/SPI4_MOSI_5") (pintype "bidirectional+no_connect"))
    )
    (net (code "96") (name "unconnected-(U1B-PE7{slash}UART7_RX-Pad37)") (class "Default")
      (node (ref "U1") (pin "37") (pinfunction "PE7/UART7_RX_37") (pintype "bidirectional+no_connect"))
    )
    (net (code "97") (name "unconnected-(U1B-PE8{slash}UART7_TX-Pad38)") (class "Default")
      (node (ref "U1") (pin "38") (pinfunction "PE8/UART7_TX_38") (pintype "bidirectional+no_connect"))
    )
    (net (code "98") (name "unconnected-(U1B-PE9{slash}TIM1_CH1-Pad39)") (class "Default")
      (node (ref "U1") (pin "39") (pinfunction "PE9/TIM1_CH1_39") (pintype "bidirectional+no_connect"))
    )
    (net (code "99") (name "unconnected-(U1B-PE10-Pad40)") (class "Default")
      (node (ref "U1") (pin "40") (pinfunction "PE10_40") (pintype "bidirectional+no_connect"))
    )
    (net (code "100") (name "unconnected-(U1B-PE11{slash}SPI4_NSS{slash}TIM1_CH2-Pad41)") (class "Default")
      (node (ref "U1") (pin "41") (pinfunction "PE11/SPI4_NSS/TIM1_CH2_41") (pintype "bidirectional+no_connect"))
    )
    (net (code "101") (name "unconnected-(U1B-PE12{slash}SPI4_SCK-Pad42)") (class "Default")
      (node (ref "U1") (pin "42") (pinfunction "PE12/SPI4_SCK_42") (pintype "bidirectional+no_connect"))
    )
    (net (code "102") (name "unconnected-(U1B-PE13{slash}SPI4_MISO{slash}TIM1_CH3-Pad43)") (class "Default")
      (node (ref "U1") (pin "43") (pinfunction "PE13/SPI4_MISO/TIM1_CH3_43") (pintype "bidirectional+no_connect"))
    )
    (net (code "103") (name "unconnected-(U1B-PE14{slash}SPI4_MOSI{slash}TIM1_CH4-Pad44)") (class "Default")
      (node (ref "U1") (pin "44") (pinfunction "PE14/SPI4_MOSI/TIM1_CH4_44") (pintype "bidirectional+no_connect"))
    )
    (net (code "104") (name "unconnected-(U1B-PE15-Pad45)") (class "Default")
      (node (ref "U1") (pin "45") (pinfunction "PE15_45") (pintype "bidirectional+no_connect"))
    )
    (net (code "105") (name "unconnected-(U1B-PH1-OSC_OUT-Pad13)") (class "Default")
      (node (ref "U1") (pin "13") (pinfunction "PH1-OSC_OUT_13") (pintype "bidirectional+no_connect"))
    )
    (net (code "106") (name "unconnected-(U3-CTS#-Pad28)") (class "Default")
      (node (ref "U3") (pin "28") (pinfunction "CTS#_28") (pintype "input+no_connect"))
    )
    (net (code "107") (name "unconnected-(U3-DCD#-Pad26)") (class "Default")
      (node (ref "U3") (pin "26") (pinfunction "DCD#_26") (pintype "input+no_connect"))
    )
    (net (code "108") (name "unconnected-(U3-DSR#-Pad7)") (class "Default")
      (node (ref "U3") (pin "7") (pinfunction "DSR#_7") (pintype "input+no_connect"))
    )
    (net (code "109") (name "unconnected-(U3-DTR#-Pad11)") (class "Default")
      (node (ref "U3") (pin "11") (pinfunction "DTR#_11") (pintype "output+no_connect"))
    )
    (net (code "110") (name "unconnected-(U3-FCE-Pad10)") (class "Default")
      (node (ref "U3") (pin "10") (pinfunction "FCE_10") (pintype "input+no_connect"))
    )
    (net (code "111") (name "unconnected-(U3-RI#-Pad27)") (class "Default")
      (node (ref "U3") (pin "27") (pinfunction "RI#_27") (pintype "input+no_connect"))
    )
    (net (code "112") (name "unconnected-(U3-RTS#-Pad25)") (class "Default")
      (node (ref "U3") (pin "25") (pinfunction "RTS#_25") (pintype "output+no_connect"))
    )
    (net (code "113") (name "unconnected-(U3-TNOW-Pad17)") (class "Default")
      (node (ref "U3") (pin "17") (pinfunction "TNOW_17") (pintype "output+no_connect"))
    )
    (net (code "114") (name "unconnected-(USB-ID-Pad4)") (class "Default")
      (node (ref "USB") (pin "4") (pinfunction "ID_4") (pintype "passive+no_connect"))
    )
  )
)
